# V5_9SMD.net
KiCad netlist of a schematic drawn in EAGLE
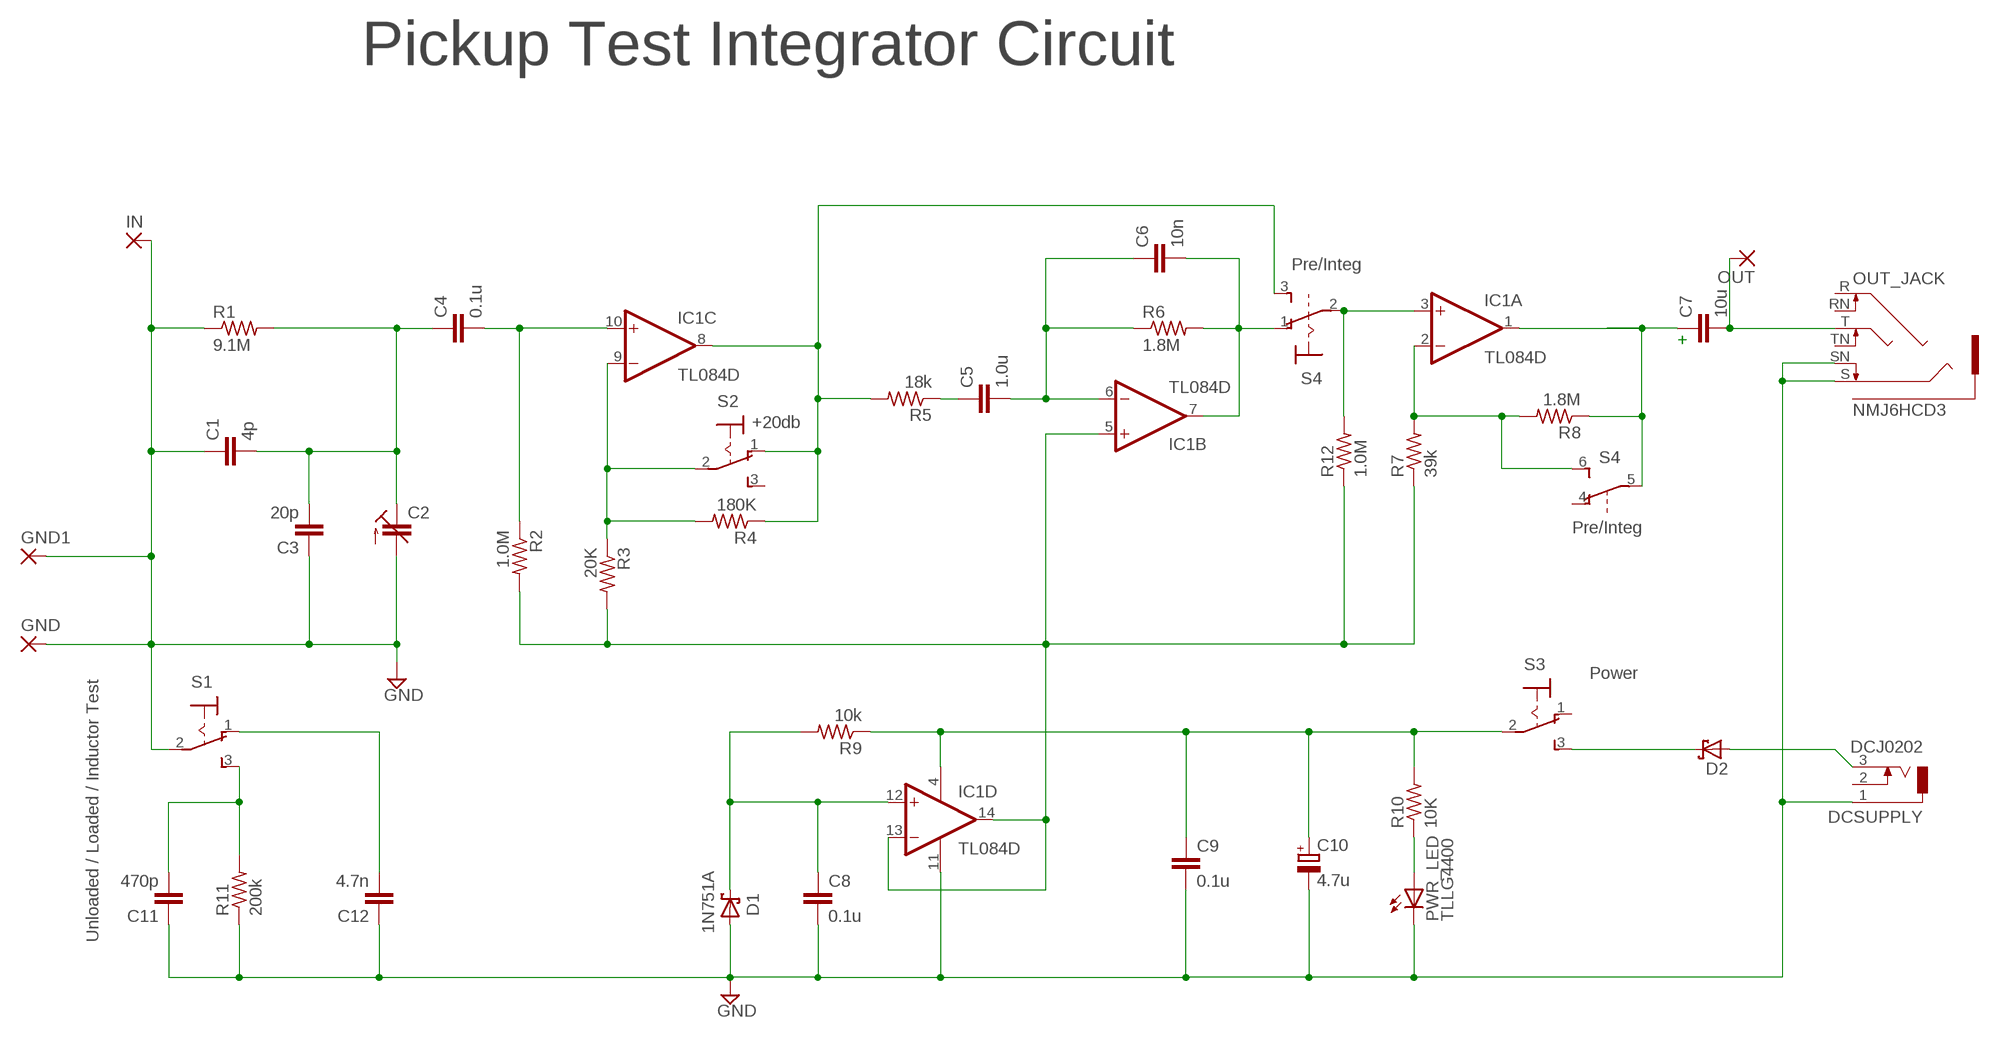
[diagram p0: schematic, sheet 1]

(export (version "E")
  (design (tool "Eeschema 10.0.6"))
  (components
    (comp (ref "C1")
      (value "4p")
      (footprint "eagle-import:C0805")
      (libsource (lib "eagle-import") (part "C-EUC0805"))
    )
    (comp (ref "C2")
      (value "C-TRIMMGKG20015")
      (footprint "eagle-import:GKG20015")
      (libsource (lib "eagle-import") (part "C-TRIMMGKG20015"))
    )
    (comp (ref "C3")
      (value "20p")
      (footprint "eagle-import:C0805")
      (libsource (lib "eagle-import") (part "C-EUC0805"))
    )
    (comp (ref "C4")
      (value "0.1u")
      (footprint "eagle-import:C0805")
      (libsource (lib "eagle-import") (part "C-EUC0805"))
    )
    (comp (ref "C5")
      (value "1.0u")
      (footprint "eagle-import:C0805")
      (libsource (lib "eagle-import") (part "C-EUC0805"))
    )
    (comp (ref "C6")
      (value "10n")
      (footprint "eagle-import:C0805")
      (libsource (lib "eagle-import") (part "C-EUC0805"))
    )
    (comp (ref "C7")
      (value "10u")
      (footprint "eagle-import:C1206K")
      (libsource (lib "eagle-import") (part "C-EUC1206K"))
    )
    (comp (ref "C8")
      (value "0.1u")
      (footprint "eagle-import:C0805")
      (libsource (lib "eagle-import") (part "C-EUC0805"))
    )
    (comp (ref "C9")
      (value "0.1u")
      (footprint "eagle-import:C0805")
      (libsource (lib "eagle-import") (part "C-EUC0805"))
    )
    (comp (ref "C10")
      (value "4.7u")
      (footprint "eagle-import:A_3216-18R")
      (libsource (lib "eagle-import") (part "CPOL-EUA/3216-18R"))
    )
    (comp (ref "C11")
      (value "470p")
      (footprint "eagle-import:C0805")
      (libsource (lib "eagle-import") (part "C-EUC0805"))
    )
    (comp (ref "C12")
      (value "4.7n")
      (footprint "eagle-import:C0805")
      (libsource (lib "eagle-import") (part "C-EUC0805"))
    )
    (comp (ref "D1")
      (value "BAS40")
      (footprint "eagle-import:SOT23")
      (libsource (lib "eagle-import") (part "BAS40"))
    )
    (comp (ref "D2")
      (value "SCHOTTKY-DIODESMD")
      (footprint "eagle-import:SMB")
      (libsource (lib "eagle-import") (part "SCHOTTKY-DIODESMD"))
    )
    (comp (ref "DCSUPPLY")
      (value "DCJ0202")
      (footprint "eagle-import:DCJ0202")
      (libsource (lib "eagle-import") (part "DCJ0202"))
    )
    (comp (ref "GND")
      (value "2,54/1,1")
      (footprint "eagle-import:2,54_1,1")
      (libsource (lib "eagle-import") (part "2,54/1,1"))
    )
    (comp (ref "GND1")
      (value "2,54/1,1")
      (footprint "eagle-import:2,54_1,1")
      (libsource (lib "eagle-import") (part "2,54/1,1"))
    )
    (comp (ref "IC1")
      (value "TL084D")
      (footprint "eagle-import:SO14")
      (libsource (lib "eagle-import") (part "TL084D"))
    )
    (comp (ref "IN")
      (value "2,54/1,1")
      (footprint "eagle-import:2,54_1,1")
      (libsource (lib "eagle-import") (part "2,54/1,1"))
    )
    (comp (ref "OUT")
      (value "2,54/1,1")
      (footprint "eagle-import:2,54_1,1")
      (libsource (lib "eagle-import") (part "2,54/1,1"))
    )
    (comp (ref "OUT_JACK")
      (value "NMJ6HCD3")
      (footprint "eagle-import:AUDIO_JACK_NEUTRIK")
      (libsource (lib "eagle-import") (part "NMJ6HCD3"))
    )
    (comp (ref "PWR_LED")
      (value "TLLG4400")
      (footprint "eagle-import:LED3MM")
      (fields (field (name "MF") "VISHAY SEMICONDUCTOR"))
      (libsource (lib "eagle-import") (part "TLLG4400"))
    )
    (comp (ref "R1")
      (value "9.1M")
      (footprint "eagle-import:R0805")
      (libsource (lib "eagle-import") (part "R-US_R0805"))
    )
    (comp (ref "R2")
      (value "1.0M")
      (footprint "eagle-import:R0805")
      (libsource (lib "eagle-import") (part "R-US_R0805"))
    )
    (comp (ref "R3")
      (value "20K")
      (footprint "eagle-import:R0805")
      (libsource (lib "eagle-import") (part "R-US_R0805"))
    )
    (comp (ref "R4")
      (value "180K")
      (footprint "eagle-import:R0805")
      (libsource (lib "eagle-import") (part "R-US_R0805"))
    )
    (comp (ref "R5")
      (value "18k")
      (footprint "eagle-import:R0805")
      (libsource (lib "eagle-import") (part "R-US_R0805"))
    )
    (comp (ref "R6")
      (value "1.8M")
      (footprint "eagle-import:R0805")
      (libsource (lib "eagle-import") (part "R-US_R0805"))
    )
    (comp (ref "R7")
      (value "39k")
      (footprint "eagle-import:R0805")
      (libsource (lib "eagle-import") (part "R-US_R0805"))
    )
    (comp (ref "R8")
      (value "1.8M")
      (footprint "eagle-import:R0805")
      (libsource (lib "eagle-import") (part "R-US_R0805"))
    )
    (comp (ref "R9")
      (value "10k")
      (footprint "eagle-import:R0805")
      (libsource (lib "eagle-import") (part "R-US_R0805"))
    )
    (comp (ref "R10")
      (value "10K")
      (footprint "eagle-import:R0805")
      (libsource (lib "eagle-import") (part "R-US_R0805"))
    )
    (comp (ref "R11")
      (value "200k")
      (footprint "eagle-import:R0805")
      (libsource (lib "eagle-import") (part "R-US_R0805"))
    )
    (comp (ref "R12")
      (value "1.0M")
      (footprint "eagle-import:R0805")
      (libsource (lib "eagle-import") (part "R-US_R0805"))
    )
    (comp (ref "S1")
      (value "320-916")
      (footprint "eagle-import:320-916")
      (libsource (lib "eagle-import") (part "320-916"))
    )
    (comp (ref "S2")
      (value "320-916")
      (footprint "eagle-import:320-916")
      (libsource (lib "eagle-import") (part "320-916"))
    )
    (comp (ref "S3")
      (value "320-916")
      (footprint "eagle-import:320-916")
      (libsource (lib "eagle-import") (part "320-916"))
    )
    (comp (ref "S4")
      (value "320-938")
      (footprint "eagle-import:320-938")
      (libsource (lib "eagle-import") (part "320-938"))
    )
  )
  (nets
    (net (code "1") (name "GND") (class "Default")
      (node (ref "C1") (pin "1") (pinfunction "1_1") (pintype "passive"))
      (node (ref "C10") (pin "-") (pinfunction "-_-") (pintype "passive"))
      (node (ref "C11") (pin "1") (pinfunction "1_1") (pintype "passive"))
      (node (ref "C12") (pin "1") (pinfunction "1_1") (pintype "passive"))
      (node (ref "C2") (pin "1") (pinfunction "A_1") (pintype "passive"))
      (node (ref "C3") (pin "1") (pinfunction "1_1") (pintype "passive"))
      (node (ref "C8") (pin "2") (pinfunction "2_2") (pintype "passive"))
      (node (ref "C9") (pin "2") (pinfunction "2_2") (pintype "passive"))
      (node (ref "D1") (pin "1") (pinfunction "A_1") (pintype "passive"))
      (node (ref "DCSUPPLY") (pin "1") (pinfunction "1_1") (pintype "passive"))
      (node (ref "GND") (pin "1") (pinfunction "P_1") (pintype "passive"))
      (node (ref "GND1") (pin "1") (pinfunction "P_1") (pintype "passive"))
      (node (ref "IC1") (pin "11") (pinfunction "V-_11") (pintype "power_in"))
      (node (ref "IN") (pin "1") (pinfunction "P_1") (pintype "passive"))
      (node (ref "OUT_JACK") (pin "S") (pinfunction "S_S") (pintype "passive"))
      (node (ref "OUT_JACK") (pin "SN") (pinfunction "SN_SN") (pintype "passive"))
      (node (ref "PWR_LED") (pin "K") (pinfunction "C_K") (pintype "passive"))
      (node (ref "R1") (pin "1") (pinfunction "1_1") (pintype "passive"))
      (node (ref "R11") (pin "1") (pinfunction "1_1") (pintype "passive"))
      (node (ref "S1") (pin "2") (pinfunction "P_2") (pintype "passive"))
    )
    (net (code "2") (name "Net-(C2-E)") (class "Default")
      (node (ref "C1") (pin "2") (pinfunction "2_2") (pintype "passive"))
      (node (ref "C2") (pin "2") (pinfunction "E_2") (pintype "passive"))
      (node (ref "C3") (pin "2") (pinfunction "2_2") (pintype "passive"))
      (node (ref "C4") (pin "1") (pinfunction "1_1") (pintype "passive"))
      (node (ref "R1") (pin "2") (pinfunction "2_2") (pintype "passive"))
    )
    (net (code "3") (name "Net-(C5-Pad1)") (class "Default")
      (node (ref "C5") (pin "1") (pinfunction "1_1") (pintype "passive"))
      (node (ref "R5") (pin "1") (pinfunction "1_1") (pintype "passive"))
    )
    (net (code "4") (name "Net-(D1-C)") (class "Default")
      (node (ref "C8") (pin "1") (pinfunction "1_1") (pintype "passive"))
      (node (ref "D1") (pin "3") (pinfunction "C_3") (pintype "passive"))
      (node (ref "IC1") (pin "12") (pinfunction "+IN_12") (pintype "input"))
      (node (ref "R9") (pin "2") (pinfunction "2_2") (pintype "passive"))
    )
    (net (code "5") (name "Net-(D2-PadA)") (class "Default")
      (node (ref "D2") (pin "A") (pinfunction "A_A") (pintype "passive"))
      (node (ref "DCSUPPLY") (pin "3") (pinfunction "3_3") (pintype "passive"))
    )
    (net (code "6") (name "Net-(IC1A-+IN)") (class "Default")
      (node (ref "IC1") (pin "3") (pinfunction "+IN_3") (pintype "input"))
      (node (ref "R12") (pin "2") (pinfunction "2_2") (pintype "passive"))
      (node (ref "S4") (pin "2") (pinfunction "P_2") (pintype "passive"))
    )
    (net (code "7") (name "Net-(IC1A--IN)") (class "Default")
      (node (ref "IC1") (pin "2") (pinfunction "-IN_2") (pintype "input"))
      (node (ref "R7") (pin "2") (pinfunction "2_2") (pintype "passive"))
      (node (ref "R8") (pin "2") (pinfunction "2_2") (pintype "passive"))
      (node (ref "S4") (pin "6") (pinfunction "S_6") (pintype "passive"))
    )
    (net (code "8") (name "Net-(IC1A-OUT)") (class "Default")
      (node (ref "C7") (pin "1") (pinfunction "1_1") (pintype "passive"))
      (node (ref "IC1") (pin "1") (pinfunction "OUT_1") (pintype "output"))
      (node (ref "R8") (pin "1") (pinfunction "1_1") (pintype "passive"))
      (node (ref "S4") (pin "5") (pinfunction "P_5") (pintype "passive"))
    )
    (net (code "9") (name "Net-(IC1B-+IN)") (class "Default")
      (node (ref "IC1") (pin "13") (pinfunction "-IN_13") (pintype "input"))
      (node (ref "IC1") (pin "14") (pinfunction "OUT_14") (pintype "output"))
      (node (ref "IC1") (pin "5") (pinfunction "+IN_5") (pintype "input"))
      (node (ref "R12") (pin "1") (pinfunction "1_1") (pintype "passive"))
      (node (ref "R2") (pin "2") (pinfunction "2_2") (pintype "passive"))
      (node (ref "R3") (pin "2") (pinfunction "2_2") (pintype "passive"))
      (node (ref "R7") (pin "1") (pinfunction "1_1") (pintype "passive"))
    )
    (net (code "10") (name "Net-(IC1B--IN)") (class "Default")
      (node (ref "C5") (pin "2") (pinfunction "2_2") (pintype "passive"))
      (node (ref "C6") (pin "1") (pinfunction "1_1") (pintype "passive"))
      (node (ref "IC1") (pin "6") (pinfunction "-IN_6") (pintype "input"))
      (node (ref "R6") (pin "1") (pinfunction "1_1") (pintype "passive"))
    )
    (net (code "11") (name "Net-(IC1B-OUT)") (class "Default")
      (node (ref "C6") (pin "2") (pinfunction "2_2") (pintype "passive"))
      (node (ref "IC1") (pin "7") (pinfunction "OUT_7") (pintype "output"))
      (node (ref "R6") (pin "2") (pinfunction "2_2") (pintype "passive"))
      (node (ref "S4") (pin "1") (pinfunction "O_1") (pintype "passive"))
    )
    (net (code "12") (name "Net-(IC1C-+IN)") (class "Default")
      (node (ref "C4") (pin "2") (pinfunction "2_2") (pintype "passive"))
      (node (ref "IC1") (pin "10") (pinfunction "+IN_10") (pintype "input"))
      (node (ref "R2") (pin "1") (pinfunction "1_1") (pintype "passive"))
    )
    (net (code "13") (name "Net-(IC1C--IN)") (class "Default")
      (node (ref "IC1") (pin "9") (pinfunction "-IN_9") (pintype "input"))
      (node (ref "R3") (pin "1") (pinfunction "1_1") (pintype "passive"))
      (node (ref "R4") (pin "2") (pinfunction "2_2") (pintype "passive"))
      (node (ref "S2") (pin "2") (pinfunction "P_2") (pintype "passive"))
    )
    (net (code "14") (name "Net-(IC1C-OUT)") (class "Default")
      (node (ref "IC1") (pin "8") (pinfunction "OUT_8") (pintype "output"))
      (node (ref "R4") (pin "1") (pinfunction "1_1") (pintype "passive"))
      (node (ref "R5") (pin "2") (pinfunction "2_2") (pintype "passive"))
      (node (ref "S2") (pin "1") (pinfunction "O_1") (pintype "passive"))
      (node (ref "S4") (pin "3") (pinfunction "S_3") (pintype "passive"))
    )
    (net (code "15") (name "Net-(IC1E-V+)") (class "Default")
      (node (ref "C10") (pin "+") (pinfunction "+_+") (pintype "passive"))
      (node (ref "C9") (pin "1") (pinfunction "1_1") (pintype "passive"))
      (node (ref "IC1") (pin "4") (pinfunction "V+_4") (pintype "power_in"))
      (node (ref "R10") (pin "2") (pinfunction "2_2") (pintype "passive"))
      (node (ref "R9") (pin "1") (pinfunction "1_1") (pintype "passive"))
      (node (ref "S3") (pin "2") (pinfunction "P_2") (pintype "passive"))
    )
    (net (code "16") (name "Net-(OUT-P)") (class "Default")
      (node (ref "C7") (pin "2") (pinfunction "2_2") (pintype "passive"))
      (node (ref "OUT") (pin "1") (pinfunction "P_1") (pintype "passive"))
      (node (ref "OUT_JACK") (pin "T") (pinfunction "T_T") (pintype "passive"))
    )
    (net (code "17") (name "Net-(PWR_LED-PadA)") (class "Default")
      (node (ref "PWR_LED") (pin "A") (pinfunction "A_A") (pintype "passive"))
      (node (ref "R10") (pin "1") (pinfunction "1_1") (pintype "passive"))
    )
    (net (code "18") (name "Net-(S1-O)") (class "Default")
      (node (ref "C12") (pin "2") (pinfunction "2_2") (pintype "passive"))
      (node (ref "S1") (pin "1") (pinfunction "O_1") (pintype "passive"))
    )
    (net (code "19") (name "Net-(S1-S)") (class "Default")
      (node (ref "C11") (pin "2") (pinfunction "2_2") (pintype "passive"))
      (node (ref "R11") (pin "2") (pinfunction "2_2") (pintype "passive"))
      (node (ref "S1") (pin "3") (pinfunction "S_3") (pintype "passive"))
    )
    (net (code "20") (name "Net-(S3-S)") (class "Default")
      (node (ref "D2") (pin "C") (pinfunction "C_C") (pintype "passive"))
      (node (ref "S3") (pin "3") (pinfunction "S_3") (pintype "passive"))
    )
    (net (code "21") (name "unconnected-(DCSUPPLY-Pad2)") (class "Default")
      (node (ref "DCSUPPLY") (pin "2") (pinfunction "2_2") (pintype "passive"))
    )
    (net (code "22") (name "unconnected-(OUT_JACK-PadR)") (class "Default")
      (node (ref "OUT_JACK") (pin "R") (pinfunction "R_R") (pintype "passive"))
    )
    (net (code "23") (name "unconnected-(OUT_JACK-PadRN)") (class "Default")
      (node (ref "OUT_JACK") (pin "RN") (pinfunction "RN_RN") (pintype "passive"))
    )
    (net (code "24") (name "unconnected-(OUT_JACK-PadTN)") (class "Default")
      (node (ref "OUT_JACK") (pin "TN") (pinfunction "TN_TN") (pintype "passive"))
    )
    (net (code "25") (name "unconnected-(S2-S-Pad3)") (class "Default")
      (node (ref "S2") (pin "3") (pinfunction "S_3") (pintype "passive"))
    )
    (net (code "26") (name "unconnected-(S3-O-Pad1)") (class "Default")
      (node (ref "S3") (pin "1") (pinfunction "O_1") (pintype "passive"))
    )
    (net (code "27") (name "unconnected-(S4B-O-Pad4)") (class "Default")
      (node (ref "S4") (pin "4") (pinfunction "O_4") (pintype "passive"))
    )
  )
)
